# XPNET_hub.net
KiCad netlist of a schematic drawn in EAGLE
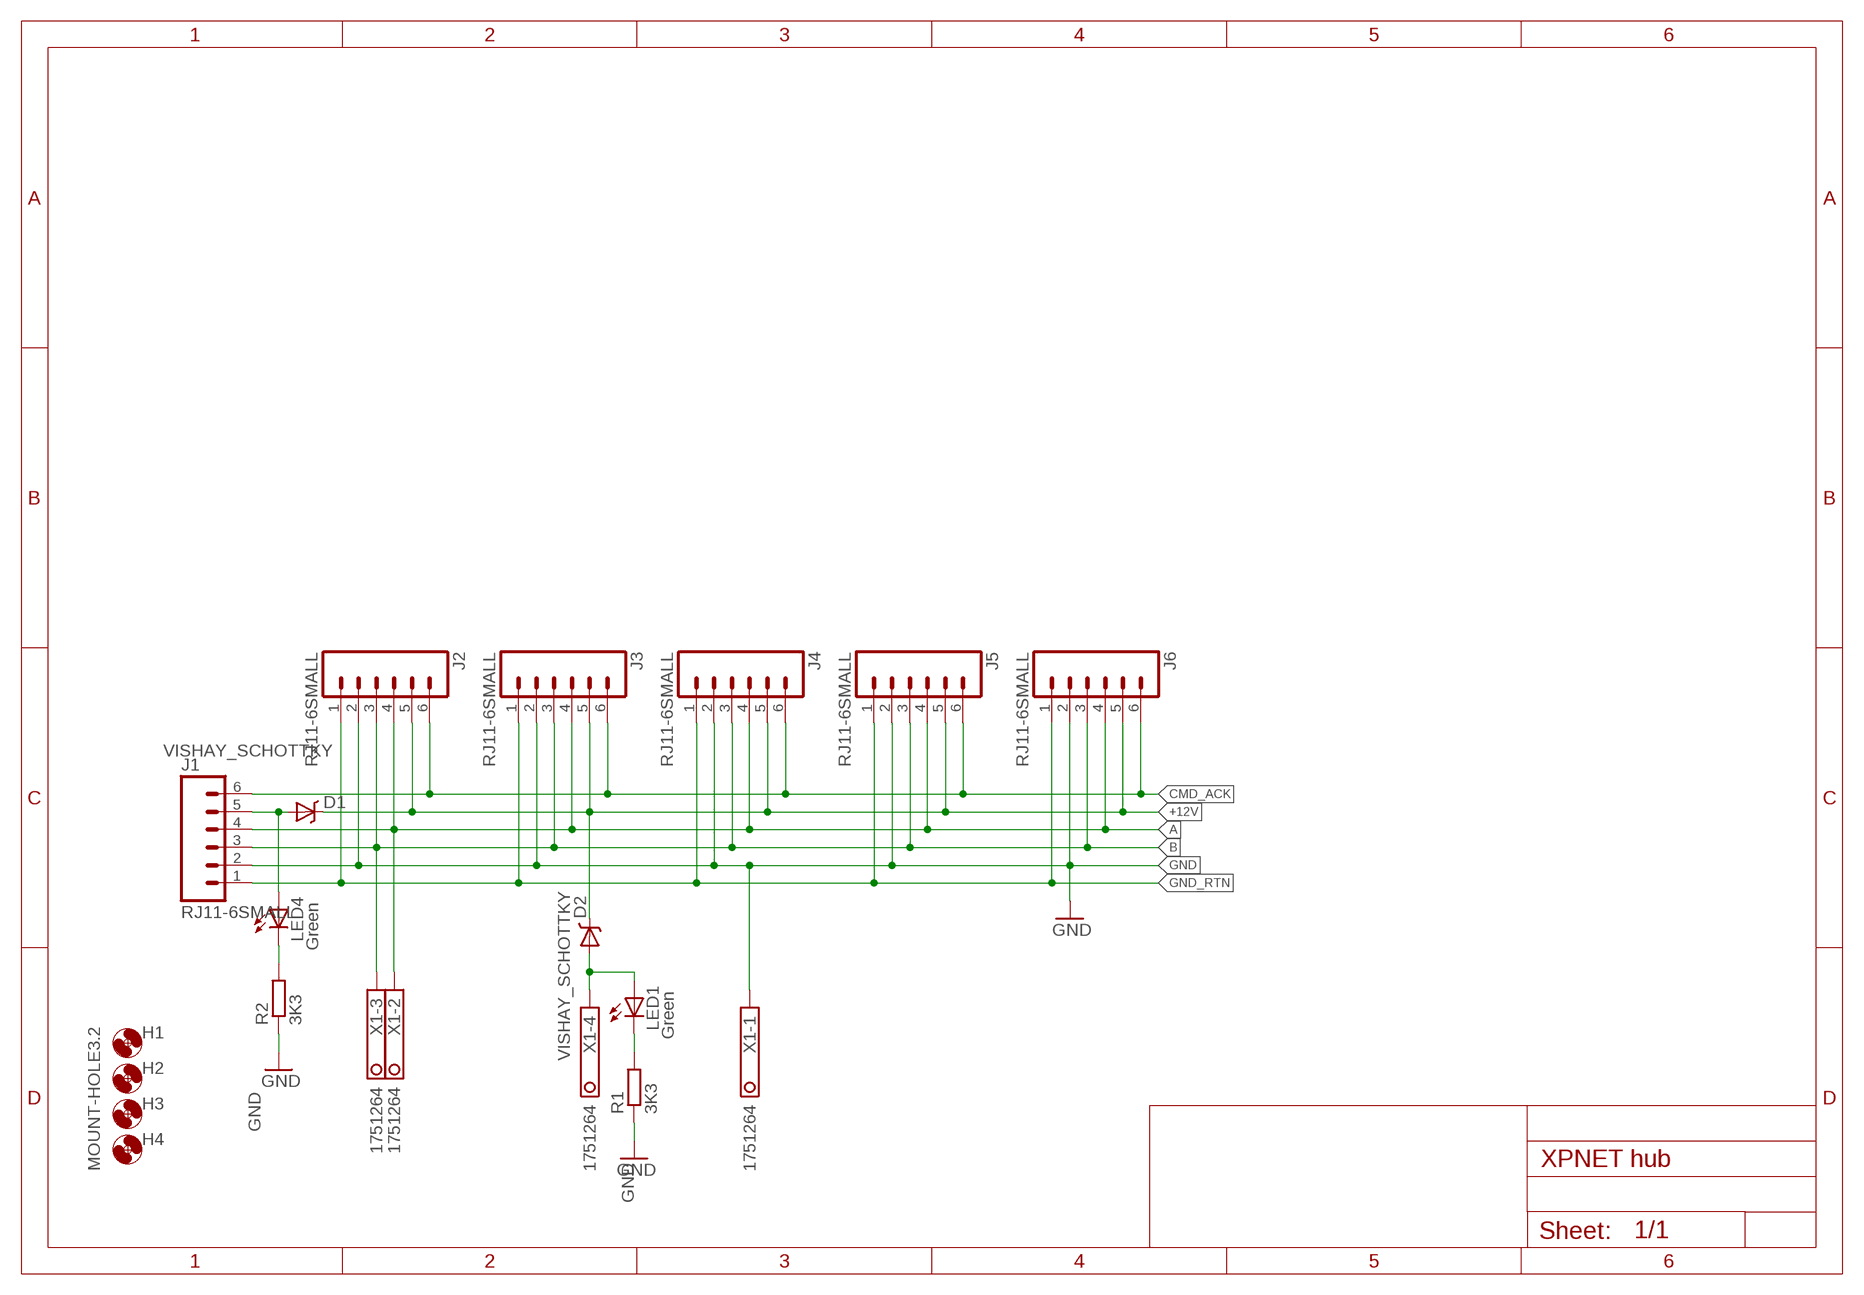
[diagram p0: schematic, sheet 1]

(export (version "E")
  (design (tool "Eeschema 10.0.6"))
  (components
    (comp (ref "D1")
      (value "VISHAY_SCHOTTKY")
      (footprint "eagle-import:DO-220AA")
      (libsource (lib "eagle-import") (part "VISHAY_SCHOTTKY"))
    )
    (comp (ref "D2")
      (value "VISHAY_SCHOTTKY")
      (footprint "eagle-import:DO-220AA")
      (libsource (lib "eagle-import") (part "VISHAY_SCHOTTKY"))
    )
    (comp (ref "H1")
      (value "MOUNT-HOLE3.2")
      (footprint "eagle-import:3,2")
      (libsource (lib "eagle-import") (part "MOUNT-HOLE3.2"))
    )
    (comp (ref "H2")
      (value "MOUNT-HOLE3.2")
      (footprint "eagle-import:3,2")
      (libsource (lib "eagle-import") (part "MOUNT-HOLE3.2"))
    )
    (comp (ref "H3")
      (value "MOUNT-HOLE3.2")
      (footprint "eagle-import:3,2")
      (libsource (lib "eagle-import") (part "MOUNT-HOLE3.2"))
    )
    (comp (ref "H4")
      (value "MOUNT-HOLE3.2")
      (footprint "eagle-import:3,2")
      (libsource (lib "eagle-import") (part "MOUNT-HOLE3.2"))
    )
    (comp (ref "J1")
      (value "RJ11-6SMALL")
      (footprint "eagle-import:RJ11-6-2")
      (libsource (lib "eagle-import") (part "RJ11-6SMALL"))
    )
    (comp (ref "J2")
      (value "RJ11-6SMALL")
      (footprint "eagle-import:RJ11-6-2")
      (libsource (lib "eagle-import") (part "RJ11-6SMALL"))
    )
    (comp (ref "J3")
      (value "RJ11-6SMALL")
      (footprint "eagle-import:RJ11-6-2")
      (libsource (lib "eagle-import") (part "RJ11-6SMALL"))
    )
    (comp (ref "J4")
      (value "RJ11-6SMALL")
      (footprint "eagle-import:RJ11-6-2")
      (libsource (lib "eagle-import") (part "RJ11-6SMALL"))
    )
    (comp (ref "J5")
      (value "RJ11-6SMALL")
      (footprint "eagle-import:RJ11-6-2")
      (libsource (lib "eagle-import") (part "RJ11-6SMALL"))
    )
    (comp (ref "J6")
      (value "RJ11-6SMALL")
      (footprint "eagle-import:RJ11-6-2")
      (libsource (lib "eagle-import") (part "RJ11-6SMALL"))
    )
    (comp (ref "LED1")
      (value "Green")
      (footprint "eagle-import:LED3MM")
      (libsource (lib "eagle-import") (part "LED3MM"))
    )
    (comp (ref "LED4")
      (value "Green")
      (footprint "eagle-import:LED3MM")
      (libsource (lib "eagle-import") (part "LED3MM"))
    )
    (comp (ref "R1")
      (value "3K3")
      (footprint "eagle-import:R0805")
      (libsource (lib "eagle-import") (part "R-EU_R0805"))
    )
    (comp (ref "R2")
      (value "3K3")
      (footprint "eagle-import:R0805")
      (libsource (lib "eagle-import") (part "R-EU_R0805"))
    )
    (comp (ref "X1")
      (value "1751264")
      (footprint "eagle-import:1751264")
      (libsource (lib "eagle-import") (part "1751264"))
    )
  )
  (nets
    (net (code "1") (name "+12V") (class "Default")
      (node (ref "D1") (pin "CATHODE") (pinfunction "C_CATHODE") (pintype "passive"))
      (node (ref "D2") (pin "CATHODE") (pinfunction "C_CATHODE") (pintype "passive"))
      (node (ref "J2") (pin "5") (pinfunction "5_5") (pintype "passive"))
      (node (ref "J3") (pin "5") (pinfunction "5_5") (pintype "passive"))
      (node (ref "J4") (pin "5") (pinfunction "5_5") (pintype "passive"))
      (node (ref "J5") (pin "5") (pinfunction "5_5") (pintype "passive"))
      (node (ref "J6") (pin "5") (pinfunction "5_5") (pintype "passive"))
    )
    (net (code "2") (name "A") (class "Default")
      (node (ref "J1") (pin "4") (pinfunction "4_4") (pintype "passive"))
      (node (ref "J2") (pin "4") (pinfunction "4_4") (pintype "passive"))
      (node (ref "J3") (pin "4") (pinfunction "4_4") (pintype "passive"))
      (node (ref "J4") (pin "4") (pinfunction "4_4") (pintype "passive"))
      (node (ref "J5") (pin "4") (pinfunction "4_4") (pintype "passive"))
      (node (ref "J6") (pin "4") (pinfunction "4_4") (pintype "passive"))
      (node (ref "X1") (pin "2") (pinfunction "K_2") (pintype "passive"))
    )
    (net (code "3") (name "B") (class "Default")
      (node (ref "J1") (pin "3") (pinfunction "3_3") (pintype "passive"))
      (node (ref "J2") (pin "3") (pinfunction "3_3") (pintype "passive"))
      (node (ref "J3") (pin "3") (pinfunction "3_3") (pintype "passive"))
      (node (ref "J4") (pin "3") (pinfunction "3_3") (pintype "passive"))
      (node (ref "J5") (pin "3") (pinfunction "3_3") (pintype "passive"))
      (node (ref "J6") (pin "3") (pinfunction "3_3") (pintype "passive"))
      (node (ref "X1") (pin "3") (pinfunction "K_3") (pintype "passive"))
    )
    (net (code "4") (name "CMD_ACK") (class "Default")
      (node (ref "J1") (pin "6") (pinfunction "6_6") (pintype "passive"))
      (node (ref "J2") (pin "6") (pinfunction "6_6") (pintype "passive"))
      (node (ref "J3") (pin "6") (pinfunction "6_6") (pintype "passive"))
      (node (ref "J4") (pin "6") (pinfunction "6_6") (pintype "passive"))
      (node (ref "J5") (pin "6") (pinfunction "6_6") (pintype "passive"))
      (node (ref "J6") (pin "6") (pinfunction "6_6") (pintype "passive"))
    )
    (net (code "5") (name "GND") (class "Default")
      (node (ref "J1") (pin "2") (pinfunction "2_2") (pintype "passive"))
      (node (ref "J2") (pin "2") (pinfunction "2_2") (pintype "passive"))
      (node (ref "J3") (pin "2") (pinfunction "2_2") (pintype "passive"))
      (node (ref "J4") (pin "2") (pinfunction "2_2") (pintype "passive"))
      (node (ref "J5") (pin "2") (pinfunction "2_2") (pintype "passive"))
      (node (ref "J6") (pin "2") (pinfunction "2_2") (pintype "passive"))
      (node (ref "R1") (pin "1") (pinfunction "1_1") (pintype "passive"))
      (node (ref "R2") (pin "1") (pinfunction "1_1") (pintype "passive"))
      (node (ref "X1") (pin "1") (pinfunction "K_1") (pintype "passive"))
    )
    (net (code "6") (name "GND_RTN") (class "Default")
      (node (ref "J1") (pin "1") (pinfunction "1_1") (pintype "passive"))
      (node (ref "J2") (pin "1") (pinfunction "1_1") (pintype "passive"))
      (node (ref "J3") (pin "1") (pinfunction "1_1") (pintype "passive"))
      (node (ref "J4") (pin "1") (pinfunction "1_1") (pintype "passive"))
      (node (ref "J5") (pin "1") (pinfunction "1_1") (pintype "passive"))
      (node (ref "J6") (pin "1") (pinfunction "1_1") (pintype "passive"))
    )
    (net (code "7") (name "Net-(D1-A)") (class "Default")
      (node (ref "D1") (pin "ANODE") (pinfunction "A_ANODE") (pintype "passive"))
      (node (ref "J1") (pin "5") (pinfunction "5_5") (pintype "passive"))
      (node (ref "LED4") (pin "A") (pinfunction "A_A") (pintype "passive"))
    )
    (net (code "8") (name "Net-(D2-A)") (class "Default")
      (node (ref "D2") (pin "ANODE") (pinfunction "A_ANODE") (pintype "passive"))
      (node (ref "LED1") (pin "A") (pinfunction "A_A") (pintype "passive"))
      (node (ref "X1") (pin "4") (pinfunction "K_4") (pintype "passive"))
    )
    (net (code "9") (name "Net-(LED1-C)") (class "Default")
      (node (ref "LED1") (pin "K") (pinfunction "C_K") (pintype "passive"))
      (node (ref "R1") (pin "2") (pinfunction "2_2") (pintype "passive"))
    )
    (net (code "10") (name "Net-(LED4-C)") (class "Default")
      (node (ref "LED4") (pin "K") (pinfunction "C_K") (pintype "passive"))
      (node (ref "R2") (pin "2") (pinfunction "2_2") (pintype "passive"))
    )
  )
)
